# arm.net
KiCad netlist of a schematic drawn in Altium Designer
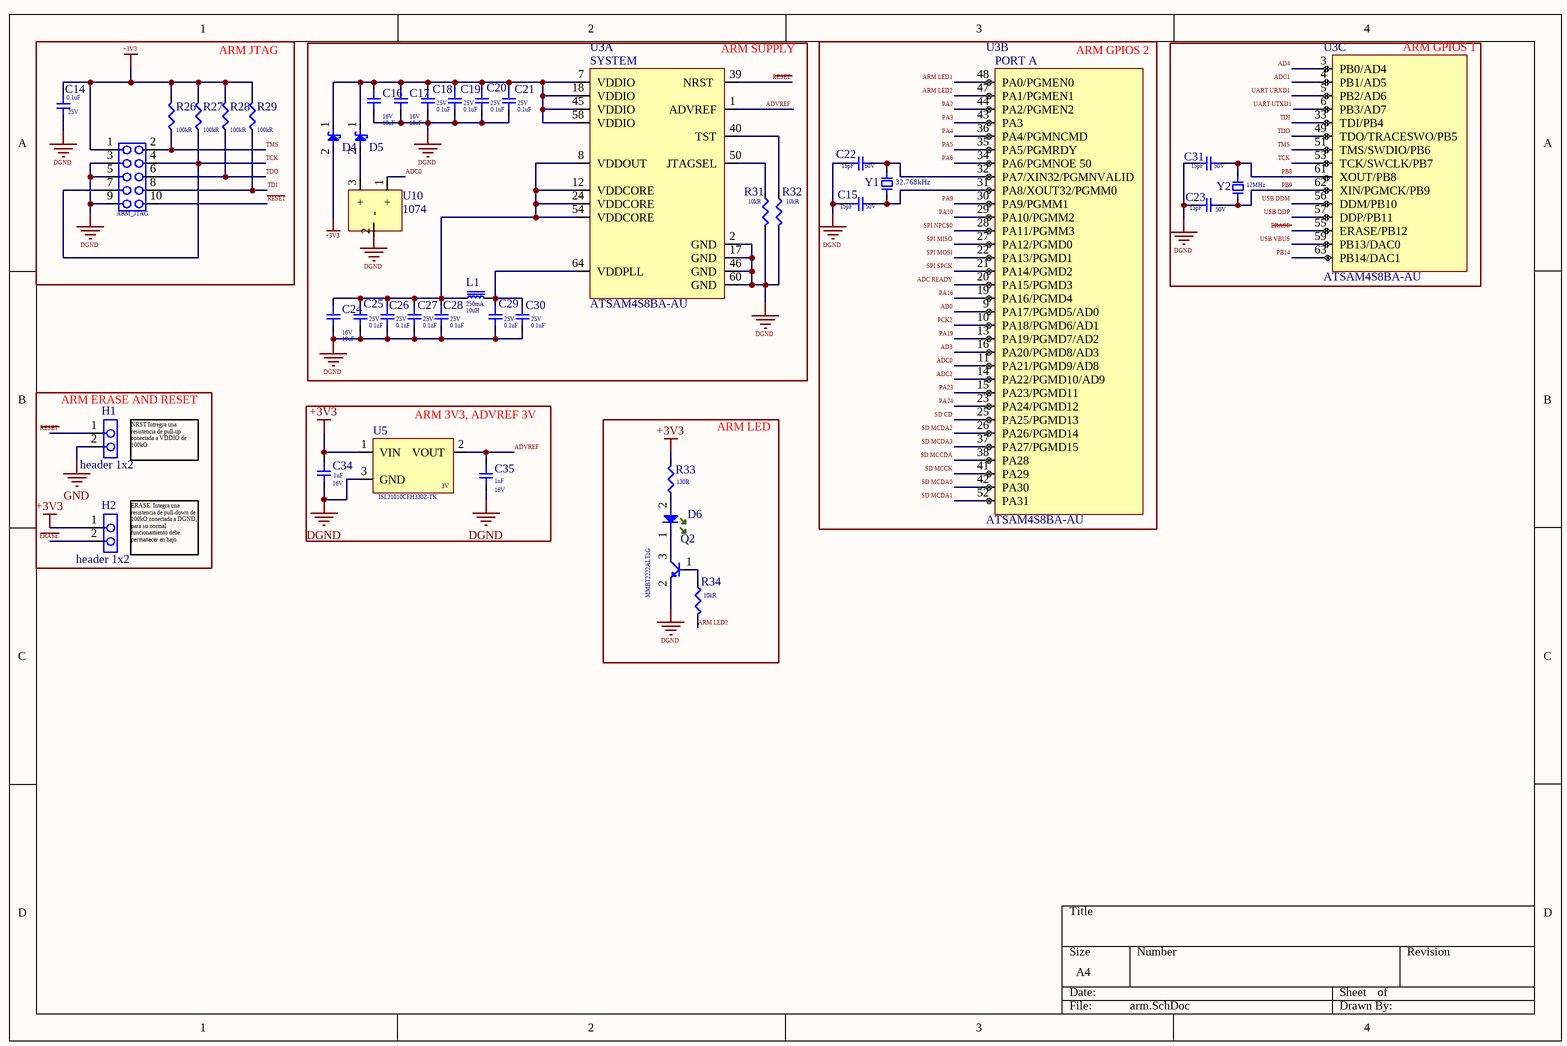
[diagram p0: arm.SchDoc]

(export (version "E")
  (design (tool "Eeschema 10.0.6"))
  (components
    (comp (ref "ARM_JTAG")
      (value "20021121-00010C4LF")
      (footprint "conector jtag ok")
      (description "Conn Unshrouded Header HDR 10 POS 1.27mm Solder ST Top Entry SMD Minitek127® T/R")
      (libsource (lib "conectors") (part "20021121-00010C4LF"))
    )
    (comp (ref "C14")
      (value "CAP_CC0805KRX7R8BB104_YAGEO")
      (footprint "CAP smd 0805 ok")
      (description "CAPACITOR, 0805, 100NF, 25V, REEL 4000")
      (fields
        (field (name "TOLERANCE") "10%")
        (field (name "VOLTAGE RATING") "25V")
        (field (name "CAPACITANCE") "0.1uF")
      )
      (libsource (lib "Cap") (part "CAP_CC0805KRX7R8BB104_YAGEO"))
    )
    (comp (ref "C15")
      (value "CAP_C0805X150J5GACTU_KEMET")
      (footprint "CAP smd 0805 ok")
      (description "Multilayer Ceramic Capacitors MLCC - SMD/SMT 50volts 15pF 5% C0G")
      (fields
        (field (name "TOLERANCE") "5%")
        (field (name "VOLTAGE RATING") "50V")
        (field (name "CAPACITANCE") "15pF")
      )
      (libsource (lib "Cap") (part "CAP_C0805X150J5GACTU_KEMET"))
    )
    (comp (ref "C16")
      (value "CAP_CL21A106KOCL3RC")
      (footprint "CAP smd 0805 OK")
      (description "CAP CER 10UF 16V X5R 0805")
      (fields
        (field (name "TOLERANCE") "10%")
        (field (name "VOLTAGE RATING") "16V")
        (field (name "CAPACITANCE") "10uF")
      )
      (libsource (lib "Cap") (part "CAP_CL21A106KOCL3RC"))
    )
    (comp (ref "C17")
      (value "CAP_CL21A106KOCL3RC")
      (footprint "CAP smd 0805 OK")
      (description "CAP CER 10UF 16V X5R 0805")
      (fields
        (field (name "TOLERANCE") "10%")
        (field (name "VOLTAGE RATING") "16V")
        (field (name "CAPACITANCE") "10uF")
      )
      (libsource (lib "Cap") (part "CAP_CL21A106KOCL3RC"))
    )
    (comp (ref "C18")
      (value "CAP_CC0805KRX7R8BB104_YAGEO")
      (footprint "CAP smd 0805 ok")
      (description "CAPACITOR, 0805, 100NF, 25V, REEL 4000")
      (fields
        (field (name "TOLERANCE") "10%")
        (field (name "VOLTAGE RATING") "25V")
        (field (name "CAPACITANCE") "0.1uF")
      )
      (libsource (lib "Cap") (part "CAP_CC0805KRX7R8BB104_YAGEO"))
    )
    (comp (ref "C19")
      (value "CAP_CC0805KRX7R8BB104_YAGEO")
      (footprint "CAP smd 0805 ok")
      (description "CAPACITOR, 0805, 100NF, 25V, REEL 4000")
      (fields
        (field (name "TOLERANCE") "10%")
        (field (name "VOLTAGE RATING") "25V")
        (field (name "CAPACITANCE") "0.1uF")
      )
      (libsource (lib "Cap") (part "CAP_CC0805KRX7R8BB104_YAGEO"))
    )
    (comp (ref "C20")
      (value "CAP_CC0805KRX7R8BB104_YAGEO")
      (footprint "CAP smd 0805 ok")
      (description "CAPACITOR, 0805, 100NF, 25V, REEL 4000")
      (fields
        (field (name "TOLERANCE") "10%")
        (field (name "VOLTAGE RATING") "25V")
        (field (name "CAPACITANCE") "0.1uF")
      )
      (libsource (lib "Cap") (part "CAP_CC0805KRX7R8BB104_YAGEO"))
    )
    (comp (ref "C21")
      (value "CAP_CC0805KRX7R8BB104_YAGEO")
      (footprint "CAP smd 0805 ok")
      (description "CAPACITOR, 0805, 100NF, 25V, REEL 4000")
      (fields
        (field (name "TOLERANCE") "10%")
        (field (name "VOLTAGE RATING") "25V")
        (field (name "CAPACITANCE") "0.1uF")
      )
      (libsource (lib "Cap") (part "CAP_CC0805KRX7R8BB104_YAGEO"))
    )
    (comp (ref "C22")
      (value "CAP_C0805X150J5GACTU_KEMET")
      (footprint "CAP smd 0805 ok")
      (description "Multilayer Ceramic Capacitors MLCC - SMD/SMT 50volts 15pF 5% C0G")
      (fields
        (field (name "TOLERANCE") "5%")
        (field (name "VOLTAGE RATING") "50V")
        (field (name "CAPACITANCE") "15pF")
      )
      (libsource (lib "Cap") (part "CAP_C0805X150J5GACTU_KEMET"))
    )
    (comp (ref "C23")
      (value "CAP_C0805X150J5GACTU_KEMET")
      (footprint "CAP smd 0805 ok")
      (description "Multilayer Ceramic Capacitors MLCC - SMD/SMT 50volts 15pF 5% C0G")
      (fields
        (field (name "TOLERANCE") "5%")
        (field (name "VOLTAGE RATING") "50V")
        (field (name "CAPACITANCE") "15pF")
      )
      (libsource (lib "Cap") (part "CAP_C0805X150J5GACTU_KEMET"))
    )
    (comp (ref "C24")
      (value "CAP_CL21A106KOCL3RC")
      (footprint "CAP smd 0805 OK")
      (description "CAP CER 10UF 16V X5R 0805")
      (fields
        (field (name "TOLERANCE") "10%")
        (field (name "VOLTAGE RATING") "16V")
        (field (name "CAPACITANCE") "10uF")
      )
      (libsource (lib "Cap") (part "CAP_CL21A106KOCL3RC"))
    )
    (comp (ref "C25")
      (value "CAP_CC0805KRX7R8BB104_YAGEO")
      (footprint "CAP smd 0805 ok")
      (description "CAPACITOR, 0805, 100NF, 25V, REEL 4000")
      (fields
        (field (name "TOLERANCE") "10%")
        (field (name "VOLTAGE RATING") "25V")
        (field (name "CAPACITANCE") "0.1uF")
      )
      (libsource (lib "Cap") (part "CAP_CC0805KRX7R8BB104_YAGEO"))
    )
    (comp (ref "C26")
      (value "CAP_CC0805KRX7R8BB104_YAGEO")
      (footprint "CAP smd 0805 ok")
      (description "CAPACITOR, 0805, 100NF, 25V, REEL 4000")
      (fields
        (field (name "TOLERANCE") "10%")
        (field (name "VOLTAGE RATING") "25V")
        (field (name "CAPACITANCE") "0.1uF")
      )
      (libsource (lib "Cap") (part "CAP_CC0805KRX7R8BB104_YAGEO"))
    )
    (comp (ref "C27")
      (value "CAP_CC0805KRX7R8BB104_YAGEO")
      (footprint "CAP smd 0805 ok")
      (description "CAPACITOR, 0805, 100NF, 25V, REEL 4000")
      (fields
        (field (name "TOLERANCE") "10%")
        (field (name "VOLTAGE RATING") "25V")
        (field (name "CAPACITANCE") "0.1uF")
      )
      (libsource (lib "Cap") (part "CAP_CC0805KRX7R8BB104_YAGEO"))
    )
    (comp (ref "C28")
      (value "CAP_CC0805KRX7R8BB104_YAGEO")
      (footprint "CAP smd 0805 ok")
      (description "CAPACITOR, 0805, 100NF, 25V, REEL 4000")
      (fields
        (field (name "TOLERANCE") "10%")
        (field (name "VOLTAGE RATING") "25V")
        (field (name "CAPACITANCE") "0.1uF")
      )
      (libsource (lib "Cap") (part "CAP_CC0805KRX7R8BB104_YAGEO"))
    )
    (comp (ref "C29")
      (value "CAP_CC0805KRX7R8BB104_YAGEO")
      (footprint "CAP smd 0805 ok")
      (description "CAPACITOR, 0805, 100NF, 25V, REEL 4000")
      (fields
        (field (name "TOLERANCE") "10%")
        (field (name "VOLTAGE RATING") "25V")
        (field (name "CAPACITANCE") "0.1uF")
      )
      (libsource (lib "Cap") (part "CAP_CC0805KRX7R8BB104_YAGEO"))
    )
    (comp (ref "C30")
      (value "CAP_CC0805KRX7R8BB104_YAGEO")
      (footprint "CAP smd 0805 ok")
      (description "CAPACITOR, 0805, 100NF, 25V, REEL 4000")
      (fields
        (field (name "TOLERANCE") "10%")
        (field (name "VOLTAGE RATING") "25V")
        (field (name "CAPACITANCE") "0.1uF")
      )
      (libsource (lib "Cap") (part "CAP_CC0805KRX7R8BB104_YAGEO"))
    )
    (comp (ref "C31")
      (value "CAP_C0805X150J5GACTU_KEMET")
      (footprint "CAP smd 0805 ok")
      (description "Multilayer Ceramic Capacitors MLCC - SMD/SMT 50volts 15pF 5% C0G")
      (fields
        (field (name "TOLERANCE") "5%")
        (field (name "VOLTAGE RATING") "50V")
        (field (name "CAPACITANCE") "15pF")
      )
      (libsource (lib "Cap") (part "CAP_C0805X150J5GACTU_KEMET"))
    )
    (comp (ref "C34")
      (value "CAP_CC0805KKX7R7BB105_YAGEO")
      (footprint "CAP smd 0805 ok")
      (description "YAGEO   CC0805KKX7R7BB105   CERAMIC CAPACITOR, 1UF, 16V, X7R, 10%, 0805")
      (fields
        (field (name "TOLERANCE") "10%")
        (field (name "VOLTAGE RATING") "16V")
        (field (name "CAPACITANCE") "1uF")
      )
      (libsource (lib "Cap") (part "CAP_CC0805KKX7R7BB105_YAGEO"))
    )
    (comp (ref "C35")
      (value "CAP_CC0805KKX7R7BB105_YAGEO")
      (footprint "CAP smd 0805 ok")
      (description "YAGEO   CC0805KKX7R7BB105   CERAMIC CAPACITOR, 1UF, 16V, X7R, 10%, 0805")
      (fields
        (field (name "TOLERANCE") "10%")
        (field (name "VOLTAGE RATING") "16V")
        (field (name "CAPACITANCE") "1uF")
      )
      (libsource (lib "Cap") (part "CAP_CC0805KKX7R7BB105_YAGEO"))
    )
    (comp (ref "D4")
      (value "DB2J20900L")
      (footprint "Diode SMini2 ok")
      (description "PANASONIC - DB2J20900L - Schottky Rectifier, 20 V, 500 mA, Single, SOD-323F, 2 Pins, 500 mV")
      (libsource (lib "diode") (part "DB2J20900L"))
    )
    (comp (ref "D5")
      (value "DB2J20900L")
      (footprint "Diode SMini2 ok")
      (description "PANASONIC - DB2J20900L - Schottky Rectifier, 20 V, 500 mA, Single, SOD-323F, 2 Pins, 500 mV")
      (libsource (lib "diode") (part "DB2J20900L"))
    )
    (comp (ref "D6")
      (value "150080VS75000")
      (footprint "Diode smd 0805 green ok")
      (description "LED GREEN CLEAR 0805 SMD")
      (libsource (lib "diode") (part "150080VS75000"))
    )
    (comp (ref "H1") (value "header 1x2") (libsource (lib "conectors") (part "header 1x2")))
    (comp (ref "H2") (value "header 1x2") (libsource (lib "conectors") (part "header 1x2")))
    (comp (ref "L1")
      (value "CM453232-100KL")
      (footprint "Inductor smd 1812 ok")
      (description "Ind General Purpose Chip Wirewound 10uH 10% 2.52MHz 50Q-Factor Ferrite 250mA 1812 T/R")
      (fields
        (field (name "TOLERANCE") "10%")
        (field (name "CURRENT RATING") "250mA")
        (field (name "INDUCTANCE") "10uH")
      )
      (libsource (lib "inductores") (part "CM453232-100KL"))
    )
    (comp (ref "Q2")
      (value "MMBT2222ALT1G")
      (footprint "transistor led ok")
      (description "Trans GP BJT NPN 40V 0.6A 3-Pin SOT-23 T/R")
      (fields (field (name "MANUFACTURER PART NUMBER 1") "MMBT2222ALT1G"))
      (libsource (lib "others") (part "MMBT2222ALT1G"))
    )
    (comp (ref "R26")
      (value "AC0805JR-07100KL")
      (footprint "res 0805 ok")
      (description "Thick Film Resistors - SMD 0805  100K ohm 5% 1/8W")
      (fields (field (name "TOLERANCE") "5%") (field (name "RESISTANCE") "100kR"))
      (libsource (lib "res") (part "AC0805JR-07100KL"))
    )
    (comp (ref "R27")
      (value "AC0805JR-07100KL")
      (footprint "res 0805 ok")
      (description "Thick Film Resistors - SMD 0805  100K ohm 5% 1/8W")
      (fields (field (name "TOLERANCE") "5%") (field (name "RESISTANCE") "100kR"))
      (libsource (lib "res") (part "AC0805JR-07100KL"))
    )
    (comp (ref "R28")
      (value "AC0805JR-07100KL")
      (footprint "res 0805 ok")
      (description "Thick Film Resistors - SMD 0805  100K ohm 5% 1/8W")
      (fields (field (name "TOLERANCE") "5%") (field (name "RESISTANCE") "100kR"))
      (libsource (lib "res") (part "AC0805JR-07100KL"))
    )
    (comp (ref "R29")
      (value "AC0805JR-07100KL")
      (footprint "res 0805 ok")
      (description "Thick Film Resistors - SMD 0805  100K ohm 5% 1/8W")
      (fields (field (name "TOLERANCE") "5%") (field (name "RESISTANCE") "100kR"))
      (libsource (lib "res") (part "AC0805JR-07100KL"))
    )
    (comp (ref "R31")
      (value "RC0805JR-0710KL")
      (footprint "res 0805 ok")
      (description "Res Thick Film smd 0805 10K Ohm 5% 1/8W")
      (fields (field (name "TOLERANCE") "5%") (field (name "RESISTANCE") "10kR"))
      (libsource (lib "res") (part "RC0805JR-0710KL"))
    )
    (comp (ref "R32")
      (value "RC0805JR-0710KL")
      (footprint "res 0805 ok")
      (description "Res Thick Film smd 0805 10K Ohm 5% 1/8W")
      (fields (field (name "TOLERANCE") "5%") (field (name "RESISTANCE") "10kR"))
      (libsource (lib "res") (part "RC0805JR-0710KL"))
    )
    (comp (ref "R33")
      (value "RC0805FR-07130RL")
      (footprint "res 0805 ok")
      (description "Res Thick Film smd 0805 130 Ohm 1% 0.125W(")
      (fields (field (name "TOLERANCE") "1%") (field (name "RESISTANCE") "130R"))
      (libsource (lib "res") (part "RC0805FR-07130RL"))
    )
    (comp (ref "R34")
      (value "RC0805JR-0710KL")
      (footprint "res 0805 ok")
      (description "Res Thick Film smd 0805 10K Ohm 5% 1/8W")
      (fields (field (name "TOLERANCE") "5%") (field (name "RESISTANCE") "10kR"))
      (libsource (lib "res") (part "RC0805JR-0710KL"))
    )
    (comp (ref "U3")
      (value "ATSAM4S8BA-AU")
      (footprint "arm ok")
      (libsource (lib "ic") (part "ATSAM4S8BA-AU"))
    )
    (comp (ref "U5")
      (value "ISL21010CFH330Z-TK")
      (footprint "3v reference ok")
      (fields
        (field (name "TOLERANCE") "0.2%")
        (field (name "MANUFACTURER PART NUMBER 1") "ISL21010CFH330Z-TK")
        (field (name "REFERENCE VOLTAGE") "3V")
      )
      (libsource (lib "ic") (part "ISL21010CFH330Z-TK"))
    )
    (comp (ref "U10")
      (value "1074")
      (footprint "pila")
      (description "Strain Relief Bushing; .437\" Mounting Hole; Black")
      (libsource (lib "conectors") (part "1074"))
    )
    (comp (ref "Y1")
      (value "ECS-.327-12.5-34S-TR")
      (footprint "clk 32k ok")
      (description "Crystal 0.032768MHz ±20ppm (Tol) 12.5pF Flexural 70000Ohm 2-Pin CSMD T/R")
      (fields (field (name "TOLERANCE") "20ppm") (field (name "FREQUENCY") "32.768kHz"))
      (libsource (lib "others") (part "ECS-.327-12.5-34S-TR"))
    )
    (comp (ref "Y2")
      (value "ECS-120-20-3X-TR")
      (footprint "clk 12M ok")
      (description "CRYSTAL 12.0000MHZ 20PF SMD")
      (fields (field (name "TOLERANCE") "30ppm") (field (name "FREQUENCY") "12MHz"))
      (libsource (lib "others") (part "ECS-120-20-3X-TR"))
    )
  )
  (nets
    (net (code "1") (name "+3V3") (class "Default")
      (node (ref "ARM_JTAG") (pin "1") (pinfunction "1_1") (pintype "passive"))
      (node (ref "C14") (pin "23") (pinfunction "23_23") (pintype "passive"))
      (node (ref "C34") (pin "23") (pinfunction "23_23") (pintype "passive"))
      (node (ref "D4") (pin "2") (pinfunction "2_2") (pintype "passive"))
      (node (ref "H2") (pin "1") (pinfunction "1_1") (pintype "passive"))
      (node (ref "R26") (pin "2") (pinfunction "2_2") (pintype "passive"))
      (node (ref "R27") (pin "2") (pinfunction "2_2") (pintype "passive"))
      (node (ref "R28") (pin "2") (pinfunction "2_2") (pintype "passive"))
      (node (ref "R29") (pin "2") (pinfunction "2_2") (pintype "passive"))
      (node (ref "R33") (pin "2") (pinfunction "2_2") (pintype "passive"))
      (node (ref "U5") (pin "1") (pinfunction "VIN_1") (pintype "passive"))
    )
    (net (code "2") (name "/AD0") (class "Default")
      (node (ref "U3") (pin "9") (pinfunction "PA17/PGMD5/AD0_9") (pintype "passive"))
    )
    (net (code "3") (name "/AD3") (class "Default")
      (node (ref "U3") (pin "16") (pinfunction "PA20/PGMD8/AD3_16") (pintype "passive"))
    )
    (net (code "4") (name "/AD4") (class "Default")
      (node (ref "U3") (pin "3") (pinfunction "PB0/AD4_3") (pintype "passive"))
    )
    (net (code "5") (name "/ADC READY") (class "Default")
      (node (ref "U3") (pin "20") (pinfunction "PA15/PGMD3_20") (pintype "passive"))
    )
    (net (code "6") (name "/ADC0") (class "Default")
      (node (ref "U10") (pin "1") (pinfunction "+_1") (pintype "passive"))
      (node (ref "U3") (pin "11") (pinfunction "PA21/PGMD9/AD8_11") (pintype "passive"))
    )
    (net (code "7") (name "/ADC1") (class "Default")
      (node (ref "U3") (pin "4") (pinfunction "PB1/AD5_4") (pintype "passive"))
    )
    (net (code "8") (name "/ADC2") (class "Default")
      (node (ref "U3") (pin "14") (pinfunction "PA22/PGMD10/AD9_14") (pintype "passive"))
    )
    (net (code "9") (name "/ADVREF") (class "Default")
      (node (ref "C35") (pin "23") (pinfunction "23_23") (pintype "passive"))
      (node (ref "U3") (pin "1") (pinfunction "ADVREF_1") (pintype "passive"))
      (node (ref "U5") (pin "2") (pinfunction "VOUT_2") (pintype "passive"))
    )
    (net (code "10") (name "/ARM LED1") (class "Default")
      (node (ref "U3") (pin "48") (pinfunction "PA0/PGMEN0_48") (pintype "passive"))
    )
    (net (code "11") (name "/ARM LED2") (class "Default")
      (node (ref "R34") (pin "1") (pintype "passive"))
      (node (ref "U3") (pin "47") (pinfunction "PA1/PGMEN1_47") (pintype "passive"))
    )
    (net (code "12") (name "/ERASE") (class "Default")
      (node (ref "H2") (pin "2") (pinfunction "2_2") (pintype "passive"))
      (node (ref "U3") (pin "55") (pinfunction "ERASE/PB12_55") (pintype "passive"))
    )
    (net (code "13") (name "/PA2") (class "Default")
      (node (ref "U3") (pin "44") (pinfunction "PA2/PGMEN2_44") (pintype "passive"))
    )
    (net (code "14") (name "/PA3") (class "Default")
      (node (ref "U3") (pin "43") (pinfunction "PA3_43") (pintype "passive"))
    )
    (net (code "15") (name "/PA4") (class "Default")
      (node (ref "U3") (pin "36") (pinfunction "PA4/PGMNCMD_36") (pintype "passive"))
    )
    (net (code "16") (name "/PA5") (class "Default")
      (node (ref "U3") (pin "35") (pinfunction "PA5/PGMRDY_35") (pintype "passive"))
    )
    (net (code "17") (name "/PA6") (class "Default")
      (node (ref "U3") (pin "34") (pinfunction "PA6/PGMNOE_50_34") (pintype "passive"))
    )
    (net (code "18") (name "/PA9") (class "Default")
      (node (ref "U3") (pin "30") (pinfunction "PA9/PGMM1_30") (pintype "passive"))
    )
    (net (code "19") (name "/PA10") (class "Default")
      (node (ref "U3") (pin "29") (pinfunction "PA10/PGMM2_29") (pintype "passive"))
    )
    (net (code "20") (name "/PA16") (class "Default")
      (node (ref "U3") (pin "19") (pinfunction "PA16/PGMD4_19") (pintype "passive"))
    )
    (net (code "21") (name "/PA19") (class "Default")
      (node (ref "U3") (pin "13") (pinfunction "PA19/PGMD7/AD2_13") (pintype "passive"))
    )
    (net (code "22") (name "/PA23") (class "Default")
      (node (ref "U3") (pin "15") (pinfunction "PA23/PGMD11_15") (pintype "passive"))
    )
    (net (code "23") (name "/PA24") (class "Default")
      (node (ref "U3") (pin "23") (pinfunction "PA24/PGMD12_23") (pintype "passive"))
    )
    (net (code "24") (name "/PB8") (class "Default")
      (node (ref "C31") (pin "23") (pinfunction "23_23") (pintype "passive"))
      (node (ref "U3") (pin "61") (pinfunction "XOUT/PB8_61") (pintype "passive"))
      (node (ref "Y2") (pin "14") (pinfunction "14_14") (pintype "passive"))
    )
    (net (code "25") (name "/PB9") (class "Default")
      (node (ref "C23") (pin "22") (pinfunction "22_22") (pintype "passive"))
      (node (ref "U3") (pin "62") (pinfunction "XIN/PGMCK/PB9_62") (pintype "passive"))
      (node (ref "Y2") (pin "13") (pinfunction "13_13") (pintype "passive"))
    )
    (net (code "26") (name "/PB14") (class "Default")
      (node (ref "U3") (pin "63") (pinfunction "PB14/DAC1_63") (pintype "passive"))
    )
    (net (code "27") (name "/PCK2") (class "Default")
      (node (ref "U3") (pin "10") (pinfunction "PA18/PGMD6/AD1_10") (pintype "passive"))
    )
    (net (code "28") (name "/RESET") (class "Default")
      (node (ref "ARM_JTAG") (pin "10") (pinfunction "10_10") (pintype "passive"))
      (node (ref "H1") (pin "1") (pinfunction "1_1") (pintype "passive"))
      (node (ref "U3") (pin "39") (pinfunction "NRST_39") (pintype "passive"))
    )
    (net (code "29") (name "/SD CD") (class "Default")
      (node (ref "U3") (pin "25") (pinfunction "PA25/PGMD13_25") (pintype "passive"))
    )
    (net (code "30") (name "/SD MCCDA") (class "Default")
      (node (ref "U3") (pin "38") (pinfunction "PA28_38") (pintype "passive"))
    )
    (net (code "31") (name "/SD MCCK") (class "Default")
      (node (ref "U3") (pin "41") (pinfunction "PA29_41") (pintype "passive"))
    )
    (net (code "32") (name "/SD MCDA0") (class "Default")
      (node (ref "U3") (pin "42") (pinfunction "PA30_42") (pintype "passive"))
    )
    (net (code "33") (name "/SD MCDA1") (class "Default")
      (node (ref "U3") (pin "52") (pinfunction "PA31_52") (pintype "passive"))
    )
    (net (code "34") (name "/SD MCDA2") (class "Default")
      (node (ref "U3") (pin "26") (pinfunction "PA26/PGMD14_26") (pintype "passive"))
    )
    (net (code "35") (name "/SD MCDA3") (class "Default")
      (node (ref "U3") (pin "37") (pinfunction "PA27/PGMD15_37") (pintype "passive"))
    )
    (net (code "36") (name "/SPI MISO") (class "Default")
      (node (ref "U3") (pin "27") (pinfunction "PA12/PGMD0_27") (pintype "passive"))
    )
    (net (code "37") (name "/SPI MOSI") (class "Default")
      (node (ref "U3") (pin "22") (pinfunction "PA13/PGMD1_22") (pintype "passive"))
    )
    (net (code "38") (name "/SPI NPCS0") (class "Default")
      (node (ref "U3") (pin "28") (pinfunction "PA11/PGMM3_28") (pintype "passive"))
    )
    (net (code "39") (name "/SPI SPCK") (class "Default")
      (node (ref "U3") (pin "21") (pinfunction "PA14/PGMD2_21") (pintype "passive"))
    )
    (net (code "40") (name "/TCK") (class "Default")
      (node (ref "ARM_JTAG") (pin "4") (pinfunction "4_4") (pintype "passive"))
      (node (ref "ARM_JTAG") (pin "7") (pinfunction "7_7") (pintype "passive"))
      (node (ref "R27") (pin "1") (pinfunction "1_1") (pintype "passive"))
      (node (ref "U3") (pin "53") (pinfunction "TCK/SWCLK/PB7_53") (pintype "passive"))
    )
    (net (code "41") (name "/TDI") (class "Default")
      (node (ref "ARM_JTAG") (pin "8") (pinfunction "8_8") (pintype "passive"))
      (node (ref "R29") (pin "1") (pinfunction "1_1") (pintype "passive"))
      (node (ref "U3") (pin "33") (pinfunction "TDI/PB4_33") (pintype "passive"))
    )
    (net (code "42") (name "/TDO") (class "Default")
      (node (ref "ARM_JTAG") (pin "6") (pinfunction "6_6") (pintype "passive"))
      (node (ref "R28") (pin "1") (pinfunction "1_1") (pintype "passive"))
      (node (ref "U3") (pin "49") (pinfunction "TDO/TRACESWO/PB5_49") (pintype "passive"))
    )
    (net (code "43") (name "/TMS") (class "Default")
      (node (ref "ARM_JTAG") (pin "2") (pinfunction "2_2") (pintype "passive"))
      (node (ref "R26") (pin "1") (pinfunction "1_1") (pintype "passive"))
      (node (ref "U3") (pin "51") (pinfunction "TMS/SWDIO/PB6_51") (pintype "passive"))
    )
    (net (code "44") (name "/UART URXD1") (class "Default")
      (node (ref "U3") (pin "5") (pinfunction "PB2/AD6_5") (pintype "passive"))
    )
    (net (code "45") (name "/UART UTXD1") (class "Default")
      (node (ref "U3") (pin "6") (pinfunction "PB3/AD7_6") (pintype "passive"))
    )
    (net (code "46") (name "/USB DDM") (class "Default")
      (node (ref "U3") (pin "56") (pinfunction "DDM/PB10_56") (pintype "passive"))
    )
    (net (code "47") (name "/USB DDP") (class "Default")
      (node (ref "U3") (pin "57") (pinfunction "DDP/PB11_57") (pintype "passive"))
    )
    (net (code "48") (name "/USB VBUS") (class "Default")
      (node (ref "U3") (pin "59") (pinfunction "PB13/DAC0_59") (pintype "passive"))
    )
    (net (code "49") (name "DGND") (class "Default")
      (node (ref "ARM_JTAG") (pin "3") (pinfunction "3_3") (pintype "passive"))
      (node (ref "ARM_JTAG") (pin "5") (pinfunction "5_5") (pintype "passive"))
      (node (ref "ARM_JTAG") (pin "9") (pinfunction "9_9") (pintype "passive"))
      (node (ref "C14") (pin "22") (pinfunction "22_22") (pintype "passive"))
      (node (ref "C15") (pin "23") (pinfunction "23_23") (pintype "passive"))
      (node (ref "C16") (pin "22") (pinfunction "22_22") (pintype "passive"))
      (node (ref "C17") (pin "22") (pinfunction "22_22") (pintype "passive"))
      (node (ref "C18") (pin "22") (pinfunction "22_22") (pintype "passive"))
      (node (ref "C19") (pin "22") (pinfunction "22_22") (pintype "passive"))
      (node (ref "C20") (pin "22") (pinfunction "22_22") (pintype "passive"))
      (node (ref "C21") (pin "22") (pinfunction "22_22") (pintype "passive"))
      (node (ref "C22") (pin "23") (pinfunction "23_23") (pintype "passive"))
      (node (ref "C23") (pin "23") (pinfunction "23_23") (pintype "passive"))
      (node (ref "C24") (pin "22") (pinfunction "22_22") (pintype "passive"))
      (node (ref "C25") (pin "22") (pinfunction "22_22") (pintype "passive"))
      (node (ref "C26") (pin "22") (pinfunction "22_22") (pintype "passive"))
      (node (ref "C27") (pin "22") (pinfunction "22_22") (pintype "passive"))
      (node (ref "C28") (pin "22") (pinfunction "22_22") (pintype "passive"))
      (node (ref "C29") (pin "22") (pinfunction "22_22") (pintype "passive"))
      (node (ref "C30") (pin "22") (pinfunction "22_22") (pintype "passive"))
      (node (ref "C31") (pin "22") (pinfunction "22_22") (pintype "passive"))
      (node (ref "C34") (pin "22") (pinfunction "22_22") (pintype "passive"))
      (node (ref "C35") (pin "22") (pinfunction "22_22") (pintype "passive"))
      (node (ref "Q2") (pin "2") (pinfunction "2_2") (pintype "passive"))
      (node (ref "R31") (pin "1") (pintype "passive"))
      (node (ref "R32") (pin "1") (pintype "passive"))
      (node (ref "U3") (pin "17") (pinfunction "GND_17") (pintype "passive"))
      (node (ref "U3") (pin "2") (pinfunction "GND_2") (pintype "passive"))
      (node (ref "U3") (pin "46") (pinfunction "GND_46") (pintype "passive"))
      (node (ref "U3") (pin "60") (pinfunction "GND_60") (pintype "passive"))
      (node (ref "U5") (pin "3") (pinfunction "GND_3") (pintype "passive"))
    )
    (net (code "50") (name "GND") (class "Default")
      (node (ref "H1") (pin "2") (pinfunction "2_2") (pintype "passive"))
    )
    (net (code "51") (name "Net-(C16-Pad23)") (class "Default")
      (node (ref "C16") (pin "23") (pinfunction "23_23") (pintype "passive"))
      (node (ref "C17") (pin "23") (pinfunction "23_23") (pintype "passive"))
      (node (ref "C18") (pin "23") (pinfunction "23_23") (pintype "passive"))
      (node (ref "C19") (pin "23") (pinfunction "23_23") (pintype "passive"))
      (node (ref "C20") (pin "23") (pinfunction "23_23") (pintype "passive"))
      (node (ref "C21") (pin "23") (pinfunction "23_23") (pintype "passive"))
      (node (ref "D4") (pin "1") (pinfunction "1_1") (pintype "passive"))
      (node (ref "D5") (pin "1") (pinfunction "1_1") (pintype "passive"))
      (node (ref "U3") (pin "18") (pinfunction "VDDIO_18") (pintype "passive"))
      (node (ref "U3") (pin "45") (pinfunction "VDDIO_45") (pintype "passive"))
      (node (ref "U3") (pin "58") (pinfunction "VDDIO_58") (pintype "passive"))
      (node (ref "U3") (pin "7") (pinfunction "VDDIO_7") (pintype "passive"))
    )
    (net (code "52") (name "Net-(D5-Pad2)") (class "Default")
      (node (ref "D5") (pin "2") (pinfunction "2_2") (pintype "passive"))
      (node (ref "U10") (pin "3") (pinfunction "+_3") (pintype "passive"))
    )
    (net (code "53") (name "Net-(D6-Pad1)") (class "Default")
      (node (ref "D6") (pin "1") (pinfunction "1_1") (pintype "passive"))
      (node (ref "Q2") (pin "3") (pinfunction "3_3") (pintype "passive"))
    )
    (net (code "54") (name "Net-(D6-Pad2)") (class "Default")
      (node (ref "D6") (pin "2") (pinfunction "2_2") (pintype "passive"))
      (node (ref "R33") (pin "1") (pinfunction "1_1") (pintype "passive"))
    )
    (net (code "55") (name "Net-(Q2-Pad1)") (class "Default")
      (node (ref "Q2") (pin "1") (pinfunction "1_1") (pintype "passive"))
      (node (ref "R34") (pin "2") (pinfunction "2_2") (pintype "passive"))
    )
    (net (code "56") (name "Net-(U3A-JTAGSEL)") (class "Default")
      (node (ref "R31") (pin "2") (pinfunction "2_2") (pintype "passive"))
      (node (ref "U3") (pin "50") (pinfunction "JTAGSEL_50") (pintype "passive"))
    )
    (net (code "57") (name "Net-(U3A-TST)") (class "Default")
      (node (ref "R32") (pin "2") (pinfunction "2_2") (pintype "passive"))
      (node (ref "U3") (pin "40") (pinfunction "TST_40") (pintype "passive"))
    )
    (net (code "58") (name "Net-(U3A-VDDOUT)") (class "Default")
      (node (ref "C24") (pin "23") (pinfunction "23_23") (pintype "passive"))
      (node (ref "C25") (pin "23") (pinfunction "23_23") (pintype "passive"))
      (node (ref "C26") (pin "23") (pinfunction "23_23") (pintype "passive"))
      (node (ref "C27") (pin "23") (pinfunction "23_23") (pintype "passive"))
      (node (ref "C28") (pin "23") (pinfunction "23_23") (pintype "passive"))
      (node (ref "L1") (pin "1") (pinfunction "1_1") (pintype "passive"))
      (node (ref "U3") (pin "12") (pinfunction "VDDCORE_12") (pintype "passive"))
      (node (ref "U3") (pin "24") (pinfunction "VDDCORE_24") (pintype "passive"))
      (node (ref "U3") (pin "54") (pinfunction "VDDCORE_54") (pintype "passive"))
      (node (ref "U3") (pin "8") (pinfunction "VDDOUT_8") (pintype "passive"))
    )
    (net (code "59") (name "Net-(U3A-VDDPLL)") (class "Default")
      (node (ref "C29") (pin "23") (pinfunction "23_23") (pintype "passive"))
      (node (ref "C30") (pin "23") (pinfunction "23_23") (pintype "passive"))
      (node (ref "L1") (pin "2") (pinfunction "2_2") (pintype "passive"))
      (node (ref "U3") (pin "64") (pinfunction "VDDPLL_64") (pintype "passive"))
    )
    (net (code "60") (name "Net-(U3B-PA7{slash}XIN32{slash}PGMNVALID)") (class "Default")
      (node (ref "C22") (pin "22") (pinfunction "22_22") (pintype "passive"))
      (node (ref "U3") (pin "32") (pinfunction "PA7/XIN32/PGMNVALID_32") (pintype "passive"))
      (node (ref "Y1") (pin "14") (pinfunction "14_14") (pintype "passive"))
    )
    (net (code "61") (name "Net-(U3B-PA8{slash}XOUT32{slash}PGMM0)") (class "Default")
      (node (ref "C15") (pin "22") (pinfunction "22_22") (pintype "passive"))
      (node (ref "U3") (pin "31") (pinfunction "PA8/XOUT32/PGMM0_31") (pintype "passive"))
      (node (ref "Y1") (pin "13") (pinfunction "13_13") (pintype "passive"))
    )
    (net (code "62") (name "unconnected-(U10---Pad2)") (class "Default")
      (node (ref "U10") (pin "2") (pinfunction "-_2") (pintype "passive"))
    )
  )
)
